# MCU_and_Sensors.net
KiCad netlist of a schematic drawn in Altium Designer
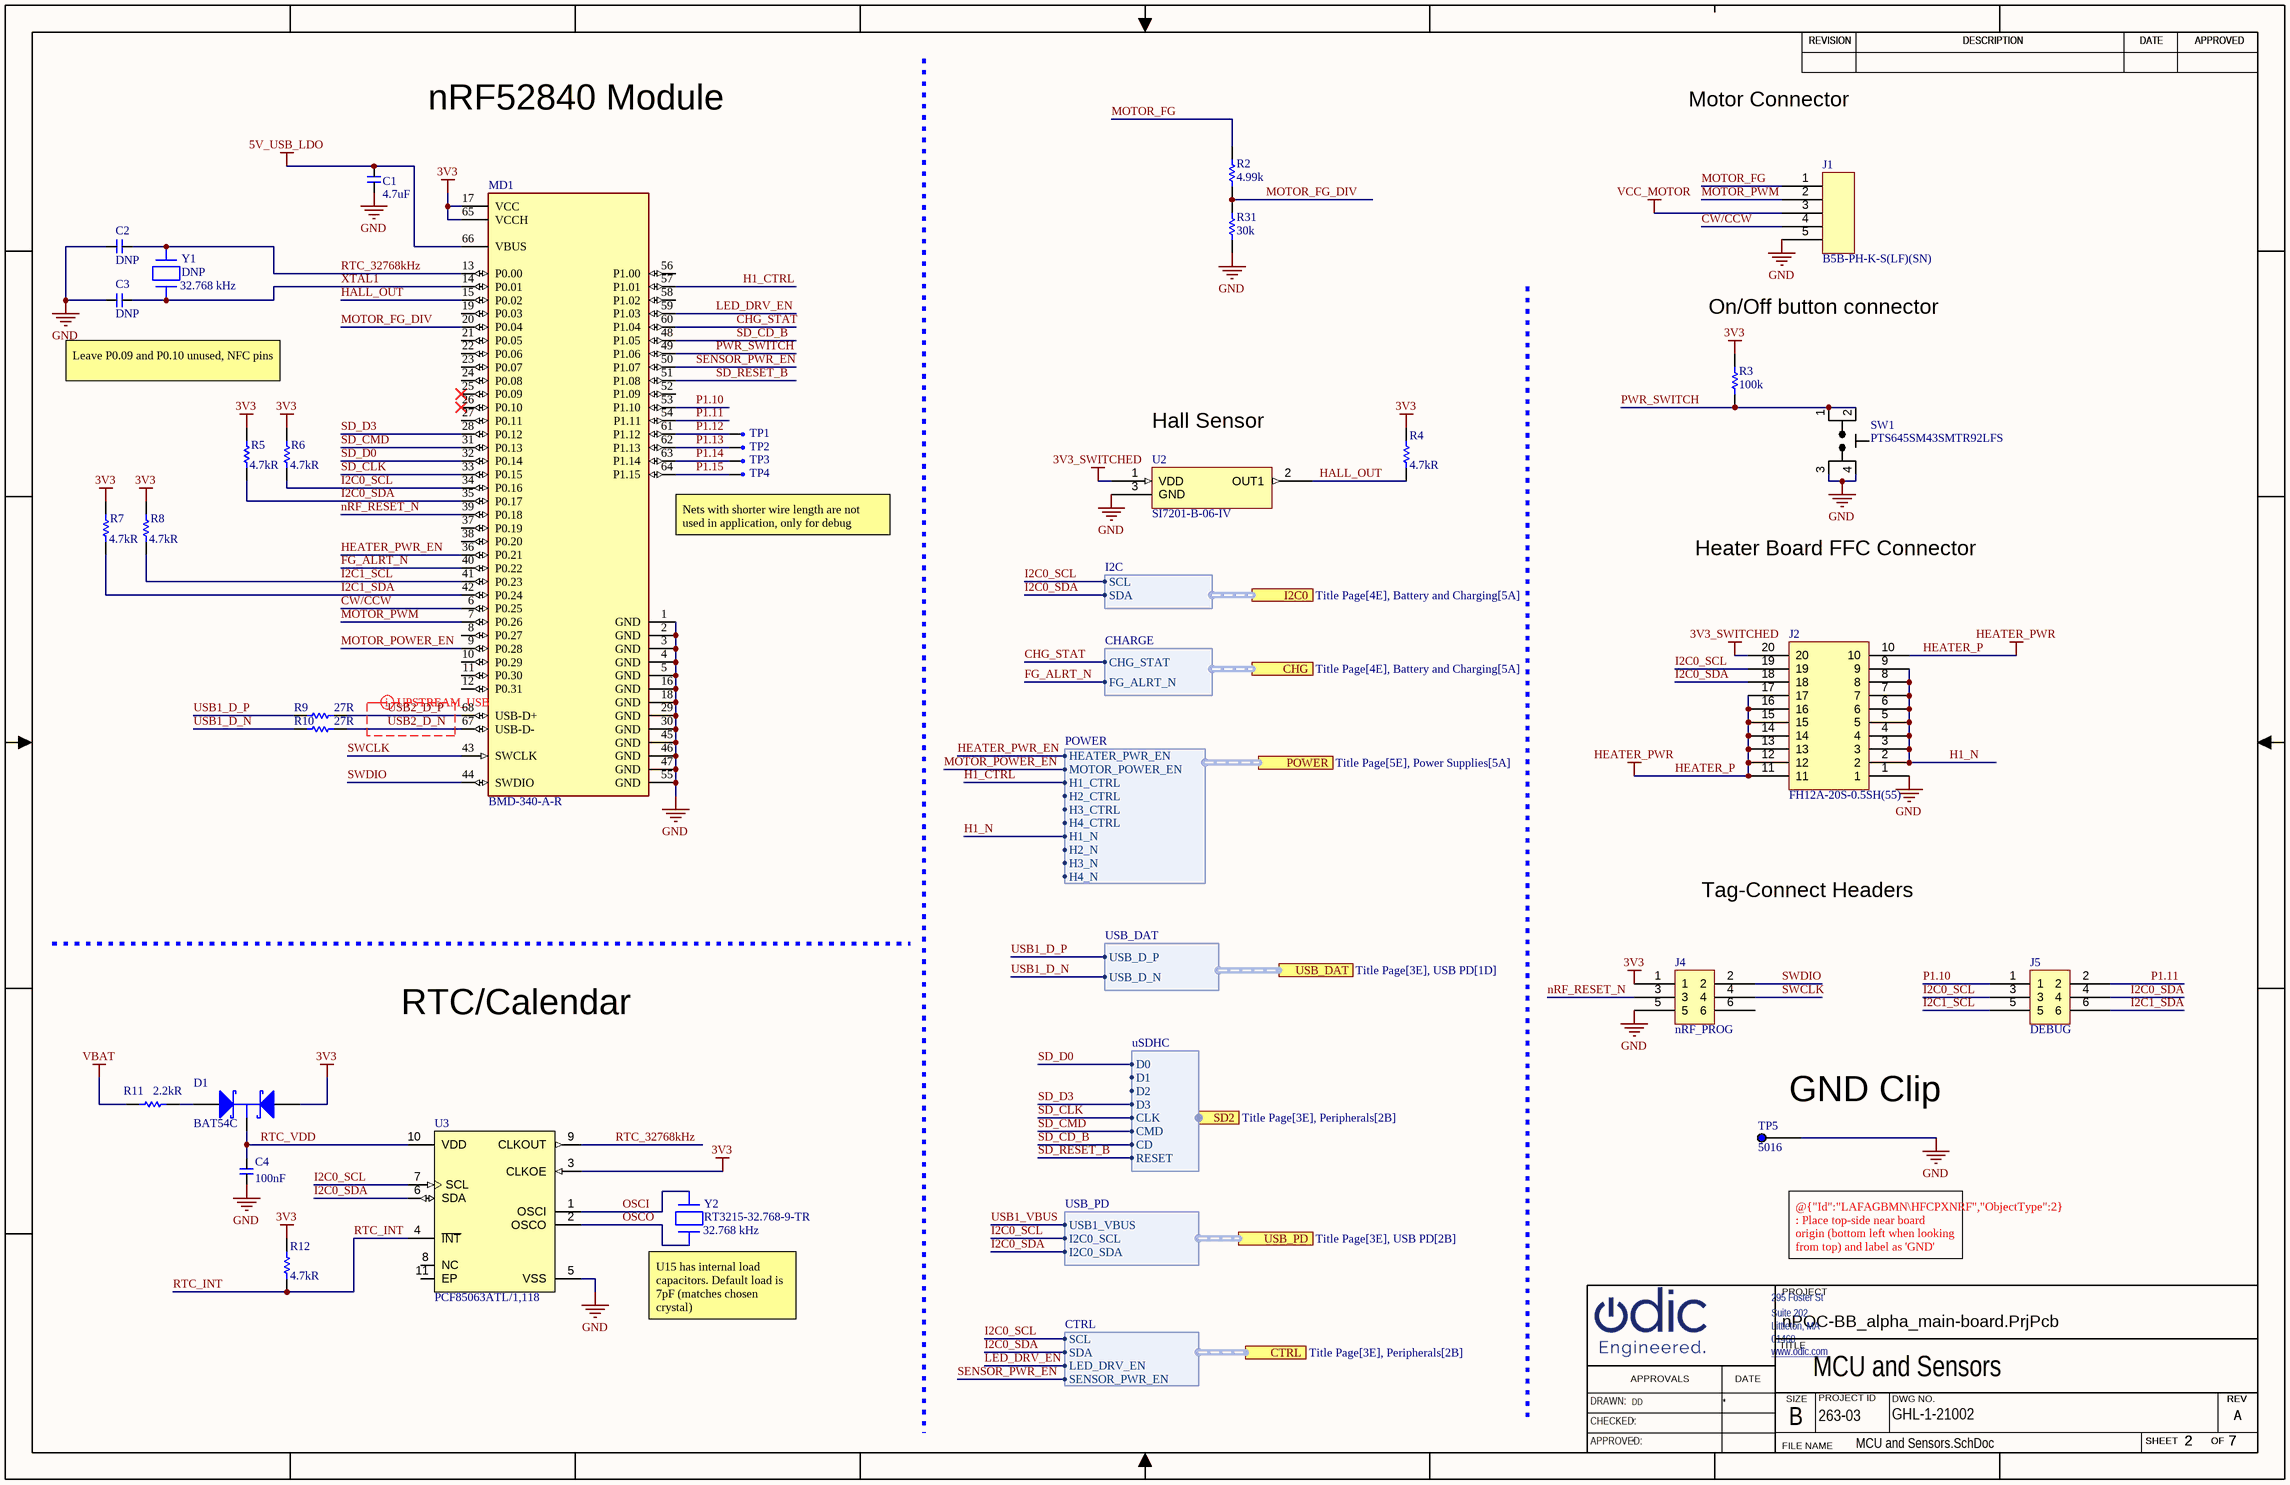
[diagram p0: MCU and Sensors.SchDoc]

(export (version "E")
  (design (tool "Eeschema 10.0.6"))
  (components
    (comp (ref "C1")
      (value "4.7uF")
      (footprint "C0603")
      (description "CAP CER 4.7UF 25V X5R 0603")
      (fields (field (name "TOLERANCE") "20%"))
      (libsource (lib "Odic Inc") (part "cAP"))
    )
    (comp (ref "C2")
      (value "DNP")
      (footprint "C0402")
      (description "Blank pads for future cap placements")
      (libsource (lib "Odic Inc") (part "cAP"))
    )
    (comp (ref "C3")
      (value "DNP")
      (footprint "C0402")
      (description "Blank pads for future cap placements")
      (libsource (lib "Odic Inc") (part "cAP"))
    )
    (comp (ref "C4")
      (value "C0402_100n_16V_10pct")
      (footprint "C0402")
      (description "0.1 µF ±10% 16V Ceramic Capacitor X7R 0402 (1005 Metric)")
      (fields
        (field (name "VOLTAGE") "16V")
        (field (name "TOLERANCE") "10%")
        (field (name "CAPACITANCE") "100nF")
      )
      (libsource (lib "Odic Inc") (part "cAP"))
    )
    (comp (ref "D1") (value "BAT54C") (footprint "SOT23") (libsource (lib "Odic Inc") (part "BAT54C-symbol")))
    (comp (ref "J1")
      (value "B5B-PH-K-S(LF)(SN)")
      (footprint "JST_B5B-PH-K-S")
      (description "Connector Header, PH Series, 5 Position, 2.00mm, Through Hole, Press-Fit, Solder, Natural")
      (libsource (lib "Odic Inc") (part "B5B-PH-K-S(LF)(SN)-Symbol-1"))
    )
    (comp (ref "J2")
      (value "FH12A-20S-0.5SH(55)")
      (footprint "hirose_fh12a-20s-0p5sh55")
      (description "Connectors for Connecting - 0.5/1-mm Pitch FPC/FFC - FH12 Series (HIROSE ELECTRIC)")
      (libsource (lib "Odic Inc") (part "FH12A-20S-0.5SH(55)-Symbol-1"))
    )
    (comp (ref "J4")
      (value "nRF_PROG")
      (footprint "tc2030-mcp-nl")
      (description "6 Pin Tag-Connect Header Footprint. Pads.")
      (libsource (lib "Odic Inc") (part "TC2030-FP-Symbol-1"))
    )
    (comp (ref "J5")
      (value "DEBUG")
      (footprint "tc2030-mcp-nl")
      (description "6 Pin Tag-Connect Header Footprint. Pads.")
      (libsource (lib "Odic Inc") (part "TC2030-FP-Symbol-1"))
    )
    (comp (ref "MD1")
      (value "BMD-340-A-R")
      (footprint "BMD-340-A-R")
      (description "BMD-340 Series 3.6 V 2.5 GHz -96 dBm Stand-Alone Bluetooth 5 Low Energy Module")
      (fields (field (name "MP") "BMD-330-A-R"))
      (libsource (lib "Odic Inc") (part "91e469dc995d0ea2fa1e7beafcd1398"))
    )
    (comp (ref "R2")
      (value "4.99k")
      (footprint "R0402")
      (description "Res General Purpose Thick Film 0402 4.99K Ohm 1% 1/16W ±100ppm/°C Molded SMD Paper T/R")
      (fields (field (name "TOLERANCE") "1%"))
      (libsource (lib "Odic Inc") (part "RES"))
    )
    (comp (ref "R3")
      (value "100k")
      (footprint "R0402")
      (description "Res General Purpose Thick Film 0402 100K Ohm 1% 1/16W ±100ppm/°C Molded SMD Paper T/R")
      (fields (field (name "TOLERANCE") "1%"))
      (libsource (lib "Odic Inc") (part "RES"))
    )
    (comp (ref "R4")
      (value "R0402_4k7_1pct")
      (footprint "R0402")
      (description "RES 4.7K OHM 1% 1/16W 0402")
      (fields (field (name "TOLERANCE") "1%") (field (name "RESISTANCE") "4.7kR"))
      (libsource (lib "Odic Inc") (part "RES"))
    )
    (comp (ref "R5")
      (value "R0402_4k7_1pct")
      (footprint "R0402")
      (description "RES 4.7K OHM 1% 1/16W 0402")
      (fields (field (name "TOLERANCE") "1%") (field (name "RESISTANCE") "4.7kR"))
      (libsource (lib "Odic Inc") (part "RES"))
    )
    (comp (ref "R6")
      (value "R0402_4k7_1pct")
      (footprint "R0402")
      (description "RES 4.7K OHM 1% 1/16W 0402")
      (fields (field (name "TOLERANCE") "1%") (field (name "RESISTANCE") "4.7kR"))
      (libsource (lib "Odic Inc") (part "RES"))
    )
    (comp (ref "R7")
      (value "R0402_4k7_1pct")
      (footprint "R0402")
      (description "RES 4.7K OHM 1% 1/16W 0402")
      (fields (field (name "TOLERANCE") "1%") (field (name "RESISTANCE") "4.7kR"))
      (libsource (lib "Odic Inc") (part "RES"))
    )
    (comp (ref "R8")
      (value "R0402_4k7_1pct")
      (footprint "R0402")
      (description "RES 4.7K OHM 1% 1/16W 0402")
      (fields (field (name "TOLERANCE") "1%") (field (name "RESISTANCE") "4.7kR"))
      (libsource (lib "Odic Inc") (part "RES"))
    )
    (comp (ref "R9")
      (value "27R")
      (footprint "R0402")
      (description "SMD Chip Resistor, 27 Ohm, ± 1%, 100 mW, 0402 [1005 Metric], Thick Film, Precision")
      (fields (field (name "TOLERANCE") "1%"))
      (libsource (lib "Odic Inc") (part "RES"))
    )
    (comp (ref "R10")
      (value "27R")
      (footprint "R0402")
      (description "SMD Chip Resistor, 27 Ohm, ± 1%, 100 mW, 0402 [1005 Metric], Thick Film, Precision")
      (fields (field (name "TOLERANCE") "1%"))
      (libsource (lib "Odic Inc") (part "RES"))
    )
    (comp (ref "R11")
      (value "R0402_2k2_5pct")
      (footprint "R0402")
      (description "Res Thick Film 0402 2.2K Ohm 5% 1/10W +/-200ppm/ßC Molded SMD Punched Carrier T/R")
      (fields (field (name "RESISTANCE") "2.2kR") (field (name "TOLERANCE") "5%"))
      (libsource (lib "Odic Inc") (part "RES"))
    )
    (comp (ref "R12")
      (value "R0402_4k7_1pct")
      (footprint "R0402")
      (description "RES 4.7K OHM 1% 1/16W 0402")
      (fields (field (name "TOLERANCE") "1%") (field (name "RESISTANCE") "4.7kR"))
      (libsource (lib "Odic Inc") (part "RES"))
    )
    (comp (ref "R31")
      (value "30k")
      (footprint "R0402")
      (description "Res General Purpose Thick Film 0402 30k Ohm 1% 1/16W ±100ppm/°C Molded Paper T/R")
      (fields (field (name "TOLERANCE") "1%"))
      (libsource (lib "Odic Inc") (part "RES"))
    )
    (comp (ref "SW1")
      (value "PTS645SM43SMTR92LFS")
      (footprint "swt_pb_pts645s")
      (description "Switch Tactile N.O. SPST Round Button Gull Wing 0.05A 12VDC 100000Cycles 1.57N SMD T/R")
      (libsource (lib "Odic Inc") (part "TL3315NF160Q-Symbol-1"))
    )
    (comp (ref "TP1")
      (value "TPC30")
      (footprint "tpc30")
      (description "Test Point Circle 30")
      (libsource (lib "Odic Inc") (part "TPC"))
    )
    (comp (ref "TP2")
      (value "TPC30")
      (footprint "tpc30")
      (description "Test Point Circle 30")
      (libsource (lib "Odic Inc") (part "TPC"))
    )
    (comp (ref "TP3")
      (value "TPC30")
      (footprint "tpc30")
      (description "Test Point Circle 30")
      (libsource (lib "Odic Inc") (part "TPC"))
    )
    (comp (ref "TP4")
      (value "TPC30")
      (footprint "tpc30")
      (description "Test Point Circle 30")
      (libsource (lib "Odic Inc") (part "TPC"))
    )
    (comp (ref "TP5")
      (value "5016")
      (footprint "KEYSTONE_5016")
      (description "Test point clip, SMT Phos Bronze/Silver 1000pc Tape & Reel")
      (libsource (lib "Odic Inc") (part "5016-Symbol-1"))
    )
    (comp (ref "U2")
      (value "SI7201-B-06-IV")
      (footprint "SOT23")
      (description "Switch/Latch Hall Effect Magnetic Position Sensor, SOT23-3, -40 to 125°C, RoHS")
      (libsource (lib "Odic Inc") (part "SI7201-B-06-IV-Symbol-1"))
    )
    (comp (ref "U3")
      (value "PCF85063ATL/1,118")
      (footprint "dfn10_2p6x2p6_p5mm")
      (description "IC RTC CLK/CALENDAR I2C 10-SON")
      (libsource (lib "Odic Inc") (part "PCF85063A"))
    )
    (comp (ref "Y1")
      (value "DNP")
      (footprint "xtal2_3p2x1p5")
      (description "RT3215 Series 0.032768 ±20 ppm 9pF -40°C TO +85°C SMT Tuning Fork Crystal")
      (fields (field (name "OPERATING FREQUENCY") "32.768 kHz"))
      (libsource (lib "Odic Inc") (part "Y*"))
    )
    (comp (ref "Y2")
      (value "RT3215-32.768-9-TR")
      (footprint "xtal2_3p2x1p5")
      (description "RT3215 Series 0.032768 ±20 ppm 9pF -40°C TO +85°C SMT Tuning Fork Crystal")
      (fields (field (name "OPERATING FREQUENCY") "32.768 kHz"))
      (libsource (lib "Odic Inc") (part "Y*"))
    )
  )
  (nets
    (net (code "8") (name "/CHG_STAT") (class "Default")
      (node (ref "MD1") (pin "60") (pinfunction "P1.04_60") (pintype "bidirectional"))
    )
    (net (code "9") (name "/CW{slash}CCW") (class "Default")
      (node (ref "J1") (pin "4") (pinfunction "4_4") (pintype "passive"))
      (node (ref "MD1") (pin "6") (pinfunction "P0.25_6") (pintype "bidirectional"))
    )
    (net (code "10") (name "/FG_ALRT_N") (class "Default")
      (node (ref "MD1") (pin "40") (pinfunction "P0.22_40") (pintype "bidirectional"))
    )
    (net (code "11") (name "/H1_CTRL") (class "Default")
      (node (ref "MD1") (pin "57") (pinfunction "P1.01_57") (pintype "bidirectional"))
    )
    (net (code "12") (name "/H1_N") (class "Default")
      (node (ref "J2") (pin "2") (pinfunction "2_2") (pintype "passive"))
      (node (ref "J2") (pin "3") (pinfunction "3_3") (pintype "passive"))
      (node (ref "J2") (pin "4") (pinfunction "4_4") (pintype "passive"))
      (node (ref "J2") (pin "5") (pinfunction "5_5") (pintype "passive"))
      (node (ref "J2") (pin "6") (pinfunction "6_6") (pintype "passive"))
      (node (ref "J2") (pin "7") (pinfunction "7_7") (pintype "passive"))
      (node (ref "J2") (pin "8") (pinfunction "8_8") (pintype "passive"))
      (node (ref "J2") (pin "9") (pinfunction "9_9") (pintype "passive"))
    )
    (net (code "13") (name "/HALL_OUT") (class "Default")
      (node (ref "MD1") (pin "15") (pinfunction "P0.02_15") (pintype "bidirectional"))
      (node (ref "R4") (pin "1") (pinfunction "1_1") (pintype "passive"))
      (node (ref "U2") (pin "2") (pinfunction "OUT1_2") (pintype "output"))
    )
    (net (code "14") (name "/HEATER_PWR_EN") (class "Default")
      (node (ref "MD1") (pin "36") (pinfunction "P0.21_36") (pintype "bidirectional"))
    )
    (net (code "15") (name "/I2C0_SCL") (class "Default")
      (node (ref "J2") (pin "19") (pinfunction "19_19") (pintype "passive"))
      (node (ref "J5") (pin "3") (pinfunction "3_3") (pintype "passive"))
      (node (ref "MD1") (pin "34") (pinfunction "P0.16_34") (pintype "bidirectional"))
      (node (ref "R6") (pin "1") (pinfunction "1_1") (pintype "passive"))
      (node (ref "U3") (pin "7") (pinfunction "SCL_7") (pintype "input"))
    )
    (net (code "16") (name "/I2C0_SDA") (class "Default")
      (node (ref "J2") (pin "18") (pinfunction "18_18") (pintype "passive"))
      (node (ref "J5") (pin "4") (pinfunction "4_4") (pintype "passive"))
      (node (ref "MD1") (pin "35") (pinfunction "P0.17_35") (pintype "bidirectional"))
      (node (ref "R5") (pin "1") (pinfunction "1_1") (pintype "passive"))
      (node (ref "U3") (pin "6") (pinfunction "SDA_6") (pintype "bidirectional"))
    )
    (net (code "17") (name "/I2C1_SCL") (class "Default")
      (node (ref "J5") (pin "5") (pinfunction "5_5") (pintype "passive"))
      (node (ref "MD1") (pin "41") (pinfunction "P0.23_41") (pintype "bidirectional"))
      (node (ref "R8") (pin "1") (pinfunction "1_1") (pintype "passive"))
    )
    (net (code "18") (name "/I2C1_SDA") (class "Default")
      (node (ref "J5") (pin "6") (pinfunction "6_6") (pintype "passive"))
      (node (ref "MD1") (pin "42") (pinfunction "P0.24_42") (pintype "bidirectional"))
      (node (ref "R7") (pin "1") (pinfunction "1_1") (pintype "passive"))
    )
    (net (code "19") (name "/LED_DRV_EN") (class "Default")
      (node (ref "MD1") (pin "59") (pinfunction "P1.03_59") (pintype "bidirectional"))
    )
    (net (code "20") (name "/MOTOR_FG") (class "Default")
      (node (ref "J1") (pin "1") (pinfunction "1_1") (pintype "passive"))
      (node (ref "R2") (pin "2") (pinfunction "2_2") (pintype "passive"))
    )
    (net (code "21") (name "/MOTOR_FG_DIV") (class "Default")
      (node (ref "MD1") (pin "20") (pinfunction "P0.04_20") (pintype "bidirectional"))
      (node (ref "R2") (pin "1") (pinfunction "1_1") (pintype "passive"))
      (node (ref "R31") (pin "2") (pinfunction "2_2") (pintype "passive"))
    )
    (net (code "22") (name "/MOTOR_POWER_EN") (class "Default")
      (node (ref "MD1") (pin "9") (pinfunction "P0.28_9") (pintype "bidirectional"))
    )
    (net (code "23") (name "/MOTOR_PWM") (class "Default")
      (node (ref "J1") (pin "2") (pinfunction "2_2") (pintype "passive"))
      (node (ref "MD1") (pin "7") (pinfunction "P0.26_7") (pintype "bidirectional"))
    )
    (net (code "24") (name "/OSCI") (class "Default")
      (node (ref "U3") (pin "1") (pinfunction "OSCI_1") (pintype "passive"))
      (node (ref "Y2") (pin "1") (pinfunction "1_1") (pintype "passive"))
    )
    (net (code "25") (name "/OSCO") (class "Default")
      (node (ref "U3") (pin "2") (pinfunction "OSCO_2") (pintype "passive"))
      (node (ref "Y2") (pin "2") (pinfunction "2_2") (pintype "passive"))
    )
    (net (code "26") (name "/P1.10") (class "Default")
      (node (ref "J5") (pin "1") (pinfunction "1_1") (pintype "passive"))
      (node (ref "MD1") (pin "53") (pinfunction "P1.10_53") (pintype "bidirectional"))
    )
    (net (code "27") (name "/P1.11") (class "Default")
      (node (ref "J5") (pin "2") (pinfunction "2_2") (pintype "passive"))
      (node (ref "MD1") (pin "54") (pinfunction "P1.11_54") (pintype "bidirectional"))
    )
    (net (code "28") (name "/P1.12") (class "Default")
      (node (ref "MD1") (pin "61") (pinfunction "P1.12_61") (pintype "bidirectional"))
      (node (ref "TP1") (pin "1") (pinfunction "1_1") (pintype "passive"))
    )
    (net (code "29") (name "/P1.13") (class "Default")
      (node (ref "MD1") (pin "62") (pinfunction "P1.13_62") (pintype "bidirectional"))
      (node (ref "TP2") (pin "1") (pinfunction "1_1") (pintype "passive"))
    )
    (net (code "30") (name "/P1.14") (class "Default")
      (node (ref "MD1") (pin "63") (pinfunction "P1.14_63") (pintype "bidirectional"))
      (node (ref "TP3") (pin "1") (pinfunction "1_1") (pintype "passive"))
    )
    (net (code "31") (name "/P1.15") (class "Default")
      (node (ref "MD1") (pin "64") (pinfunction "P1.15_64") (pintype "bidirectional"))
      (node (ref "TP4") (pin "1") (pinfunction "1_1") (pintype "passive"))
    )
    (net (code "32") (name "/PWR_SWITCH") (class "Default")
      (node (ref "MD1") (pin "49") (pinfunction "P1.06_49") (pintype "bidirectional"))
      (node (ref "R3") (pin "1") (pinfunction "1_1") (pintype "passive"))
      (node (ref "SW1") (pin "1") (pinfunction "1_1") (pintype "passive"))
      (node (ref "SW1") (pin "2") (pinfunction "2_2") (pintype "passive"))
    )
    (net (code "33") (name "/RTC_32768kHz") (class "Default")
      (node (ref "C2") (pin "2") (pinfunction "2_2") (pintype "passive"))
      (node (ref "MD1") (pin "13") (pinfunction "P0.00_13") (pintype "bidirectional"))
      (node (ref "U3") (pin "9") (pinfunction "CLKOUT_9") (pintype "output"))
      (node (ref "Y1") (pin "1") (pinfunction "1_1") (pintype "passive"))
    )
    (net (code "34") (name "/RTC_INT") (class "Default")
      (node (ref "R12") (pin "1") (pinfunction "1_1") (pintype "passive"))
      (node (ref "U3") (pin "4") (pinfunction "~{INT}_4") (pintype "open_collector"))
    )
    (net (code "35") (name "/RTC_VDD") (class "Default")
      (node (ref "C4") (pin "1") (pinfunction "1_1") (pintype "passive"))
      (node (ref "D1") (pin "3") (pinfunction "K_3") (pintype "passive"))
      (node (ref "U3") (pin "10") (pinfunction "VDD_10") (pintype "power_in"))
    )
    (net (code "36") (name "/SD_CD_B") (class "Default")
      (node (ref "MD1") (pin "48") (pinfunction "P1.05_48") (pintype "bidirectional"))
    )
    (net (code "37") (name "/SD_CLK") (class "Default")
      (node (ref "MD1") (pin "33") (pinfunction "P0.15_33") (pintype "bidirectional"))
    )
    (net (code "38") (name "/SD_CMD") (class "Default")
      (node (ref "MD1") (pin "31") (pinfunction "P0.13_31") (pintype "bidirectional"))
    )
    (net (code "39") (name "/SD_D0") (class "Default")
      (node (ref "MD1") (pin "32") (pinfunction "P0.14_32") (pintype "bidirectional"))
    )
    (net (code "40") (name "/SD_D3") (class "Default")
      (node (ref "MD1") (pin "28") (pinfunction "P0.12_28") (pintype "bidirectional"))
    )
    (net (code "41") (name "/SD_RESET_B") (class "Default")
      (node (ref "MD1") (pin "51") (pinfunction "P1.08_51") (pintype "bidirectional"))
    )
    (net (code "42") (name "/SENSOR_PWR_EN") (class "Default")
      (node (ref "MD1") (pin "50") (pinfunction "P1.07_50") (pintype "bidirectional"))
    )
    (net (code "43") (name "/SWCLK") (class "Default")
      (node (ref "J4") (pin "4") (pinfunction "4_4") (pintype "passive"))
      (node (ref "MD1") (pin "43") (pinfunction "SWCLK_43") (pintype "input"))
    )
    (net (code "44") (name "/SWDIO") (class "Default")
      (node (ref "J4") (pin "2") (pinfunction "2_2") (pintype "passive"))
      (node (ref "MD1") (pin "44") (pinfunction "SWDIO_44") (pintype "bidirectional"))
    )
    (net (code "45") (name "/USB1_D_N") (class "Default")
      (node (ref "R10") (pin "1") (pinfunction "1_1") (pintype "passive"))
    )
    (net (code "46") (name "/USB1_D_P") (class "Default")
      (node (ref "R9") (pin "1") (pinfunction "1_1") (pintype "passive"))
    )
    (net (code "48") (name "/USB2_D_N") (class "Default")
      (node (ref "MD1") (pin "67") (pinfunction "USB-D-_67") (pintype "bidirectional"))
      (node (ref "R10") (pin "2") (pinfunction "2_2") (pintype "passive"))
    )
    (net (code "49") (name "/USB2_D_P") (class "Default")
      (node (ref "MD1") (pin "68") (pinfunction "USB-D+_68") (pintype "bidirectional"))
      (node (ref "R9") (pin "2") (pinfunction "2_2") (pintype "passive"))
    )
    (net (code "50") (name "/XTAL1") (class "Default")
      (node (ref "C3") (pin "2") (pinfunction "2_2") (pintype "passive"))
      (node (ref "MD1") (pin "14") (pinfunction "P0.01_14") (pintype "bidirectional"))
      (node (ref "Y1") (pin "2") (pinfunction "2_2") (pintype "passive"))
    )
    (net (code "51") (name "/nRF_RESET_N") (class "Default")
      (node (ref "J4") (pin "3") (pinfunction "3_3") (pintype "passive"))
      (node (ref "MD1") (pin "39") (pinfunction "P0.18_39") (pintype "bidirectional"))
    )
    (net (code "59") (name "3V3") (class "Default")
      (node (ref "D1") (pin "2") (pinfunction "A2_2") (pintype "passive"))
      (node (ref "J4") (pin "1") (pinfunction "1_1") (pintype "passive"))
      (node (ref "MD1") (pin "17") (pinfunction "VCC_17") (pintype "power_in"))
      (node (ref "MD1") (pin "65") (pinfunction "VCCH_65") (pintype "power_in"))
      (node (ref "R12") (pin "2") (pinfunction "2_2") (pintype "passive"))
      (node (ref "R3") (pin "2") (pinfunction "2_2") (pintype "passive"))
      (node (ref "R4") (pin "2") (pinfunction "2_2") (pintype "passive"))
      (node (ref "R5") (pin "2") (pinfunction "2_2") (pintype "passive"))
      (node (ref "R6") (pin "2") (pinfunction "2_2") (pintype "passive"))
      (node (ref "R7") (pin "2") (pinfunction "2_2") (pintype "passive"))
      (node (ref "R8") (pin "2") (pinfunction "2_2") (pintype "passive"))
      (node (ref "U3") (pin "3") (pinfunction "CLKOE_3") (pintype "input"))
    )
    (net (code "60") (name "3V3_SWITCHED") (class "Default")
      (node (ref "J2") (pin "20") (pinfunction "20_20") (pintype "passive"))
      (node (ref "U2") (pin "1") (pinfunction "VDD_1") (pintype "input"))
    )
    (net (code "61") (name "5V_USB_LDO") (class "Default")
      (node (ref "C1") (pin "2") (pinfunction "2_2") (pintype "passive"))
      (node (ref "MD1") (pin "66") (pinfunction "VBUS_66") (pintype "power_in"))
    )
    (net (code "62") (name "GND") (class "Default")
      (node (ref "C1") (pin "1") (pinfunction "1_1") (pintype "passive"))
      (node (ref "C2") (pin "1") (pinfunction "1_1") (pintype "passive"))
      (node (ref "C3") (pin "1") (pinfunction "1_1") (pintype "passive"))
      (node (ref "C4") (pin "2") (pinfunction "2_2") (pintype "passive"))
      (node (ref "J1") (pin "5") (pinfunction "5_5") (pintype "passive"))
      (node (ref "J2") (pin "1") (pinfunction "1_1") (pintype "passive"))
      (node (ref "J4") (pin "5") (pinfunction "5_5") (pintype "passive"))
      (node (ref "MD1") (pin "1") (pinfunction "GND_1") (pintype "power_in"))
      (node (ref "MD1") (pin "16") (pinfunction "GND_16") (pintype "power_in"))
      (node (ref "MD1") (pin "18") (pinfunction "GND_18") (pintype "power_in"))
      (node (ref "MD1") (pin "2") (pinfunction "GND_2") (pintype "power_in"))
      (node (ref "MD1") (pin "29") (pinfunction "GND_29") (pintype "power_in"))
      (node (ref "MD1") (pin "3") (pinfunction "GND_3") (pintype "power_in"))
      (node (ref "MD1") (pin "30") (pinfunction "GND_30") (pintype "power_in"))
      (node (ref "MD1") (pin "4") (pinfunction "GND_4") (pintype "power_in"))
      (node (ref "MD1") (pin "45") (pinfunction "GND_45") (pintype "power_in"))
      (node (ref "MD1") (pin "46") (pinfunction "GND_46") (pintype "power_in"))
      (node (ref "MD1") (pin "47") (pinfunction "GND_47") (pintype "power_in"))
      (node (ref "MD1") (pin "5") (pinfunction "GND_5") (pintype "power_in"))
      (node (ref "MD1") (pin "55") (pinfunction "GND_55") (pintype "power_in"))
      (node (ref "R31") (pin "1") (pinfunction "1_1") (pintype "passive"))
      (node (ref "SW1") (pin "3") (pinfunction "3_3") (pintype "passive"))
      (node (ref "SW1") (pin "4") (pinfunction "4_4") (pintype "passive"))
      (node (ref "TP5") (pin "1") (pinfunction "1_1") (pintype "passive"))
      (node (ref "U2") (pin "3") (pinfunction "GND_3") (pintype "passive"))
      (node (ref "U3") (pin "5") (pinfunction "VSS_5") (pintype "power_in"))
    )
    (net (code "63") (name "HEATER_PWR") (class "Default")
      (node (ref "J2") (pin "10") (pinfunction "10_10") (pintype "passive"))
      (node (ref "J2") (pin "11") (pinfunction "11_11") (pintype "passive"))
      (node (ref "J2") (pin "12") (pinfunction "12_12") (pintype "passive"))
      (node (ref "J2") (pin "13") (pinfunction "13_13") (pintype "passive"))
      (node (ref "J2") (pin "14") (pinfunction "14_14") (pintype "passive"))
      (node (ref "J2") (pin "15") (pinfunction "15_15") (pintype "passive"))
      (node (ref "J2") (pin "16") (pinfunction "16_16") (pintype "passive"))
      (node (ref "J2") (pin "17") (pinfunction "17_17") (pintype "passive"))
    )
    (net (code "64") (name "Net-(D1-A1)") (class "Default")
      (node (ref "D1") (pin "1") (pinfunction "A1_1") (pintype "passive"))
      (node (ref "R11") (pin "2") (pinfunction "2_2") (pintype "passive"))
    )
    (net (code "65") (name "VBAT") (class "Default")
      (node (ref "R11") (pin "1") (pinfunction "1_1") (pintype "passive"))
    )
    (net (code "66") (name "VCC_MOTOR") (class "Default")
      (node (ref "J1") (pin "3") (pinfunction "3_3") (pintype "passive"))
    )
    (net (code "67") (name "unconnected-(J4-Pad6)") (class "Default")
      (node (ref "J4") (pin "6") (pinfunction "6_6") (pintype "passive"))
    )
    (net (code "68") (name "unconnected-(MD1-P0.03-Pad19)") (class "Default")
      (node (ref "MD1") (pin "19") (pinfunction "P0.03_19") (pintype "bidirectional"))
    )
    (net (code "69") (name "unconnected-(MD1-P0.05-Pad21)") (class "Default")
      (node (ref "MD1") (pin "21") (pinfunction "P0.05_21") (pintype "bidirectional"))
    )
    (net (code "70") (name "unconnected-(MD1-P0.06-Pad22)") (class "Default")
      (node (ref "MD1") (pin "22") (pinfunction "P0.06_22") (pintype "bidirectional"))
    )
    (net (code "71") (name "unconnected-(MD1-P0.07-Pad23)") (class "Default")
      (node (ref "MD1") (pin "23") (pinfunction "P0.07_23") (pintype "bidirectional"))
    )
    (net (code "72") (name "unconnected-(MD1-P0.08-Pad24)") (class "Default")
      (node (ref "MD1") (pin "24") (pinfunction "P0.08_24") (pintype "bidirectional"))
    )
    (net (code "73") (name "unconnected-(MD1-P0.09-Pad25)") (class "Default")
      (node (ref "MD1") (pin "25") (pinfunction "P0.09_25") (pintype "bidirectional+no_connect"))
    )
    (net (code "74") (name "unconnected-(MD1-P0.10-Pad26)") (class "Default")
      (node (ref "MD1") (pin "26") (pinfunction "P0.10_26") (pintype "bidirectional+no_connect"))
    )
    (net (code "75") (name "unconnected-(MD1-P0.11-Pad27)") (class "Default")
      (node (ref "MD1") (pin "27") (pinfunction "P0.11_27") (pintype "bidirectional"))
    )
    (net (code "76") (name "unconnected-(MD1-P0.19-Pad37)") (class "Default")
      (node (ref "MD1") (pin "37") (pinfunction "P0.19_37") (pintype "bidirectional"))
    )
    (net (code "77") (name "unconnected-(MD1-P0.20-Pad38)") (class "Default")
      (node (ref "MD1") (pin "38") (pinfunction "P0.20_38") (pintype "bidirectional"))
    )
    (net (code "78") (name "unconnected-(MD1-P0.27-Pad8)") (class "Default")
      (node (ref "MD1") (pin "8") (pinfunction "P0.27_8") (pintype "bidirectional"))
    )
    (net (code "79") (name "unconnected-(MD1-P0.29-Pad10)") (class "Default")
      (node (ref "MD1") (pin "10") (pinfunction "P0.29_10") (pintype "bidirectional"))
    )
    (net (code "80") (name "unconnected-(MD1-P0.30-Pad11)") (class "Default")
      (node (ref "MD1") (pin "11") (pinfunction "P0.30_11") (pintype "bidirectional"))
    )
    (net (code "81") (name "unconnected-(MD1-P0.31-Pad12)") (class "Default")
      (node (ref "MD1") (pin "12") (pinfunction "P0.31_12") (pintype "bidirectional"))
    )
    (net (code "82") (name "unconnected-(MD1-P1.00-Pad56)") (class "Default")
      (node (ref "MD1") (pin "56") (pinfunction "P1.00_56") (pintype "bidirectional"))
    )
    (net (code "83") (name "unconnected-(MD1-P1.02-Pad58)") (class "Default")
      (node (ref "MD1") (pin "58") (pinfunction "P1.02_58") (pintype "bidirectional"))
    )
    (net (code "84") (name "unconnected-(MD1-P1.09-Pad52)") (class "Default")
      (node (ref "MD1") (pin "52") (pinfunction "P1.09_52") (pintype "bidirectional"))
    )
    (net (code "85") (name "unconnected-(U3-EP-Pad11)") (class "Default")
      (node (ref "U3") (pin "11") (pinfunction "EP_11") (pintype "power_in"))
    )
    (net (code "86") (name "unconnected-(U3-NC-Pad8)") (class "Default")
      (node (ref "U3") (pin "8") (pinfunction "NC_8") (pintype "passive"))
    )
  )
)
